# Main_Design.net
KiCad netlist of a schematic drawn in Altium Designer
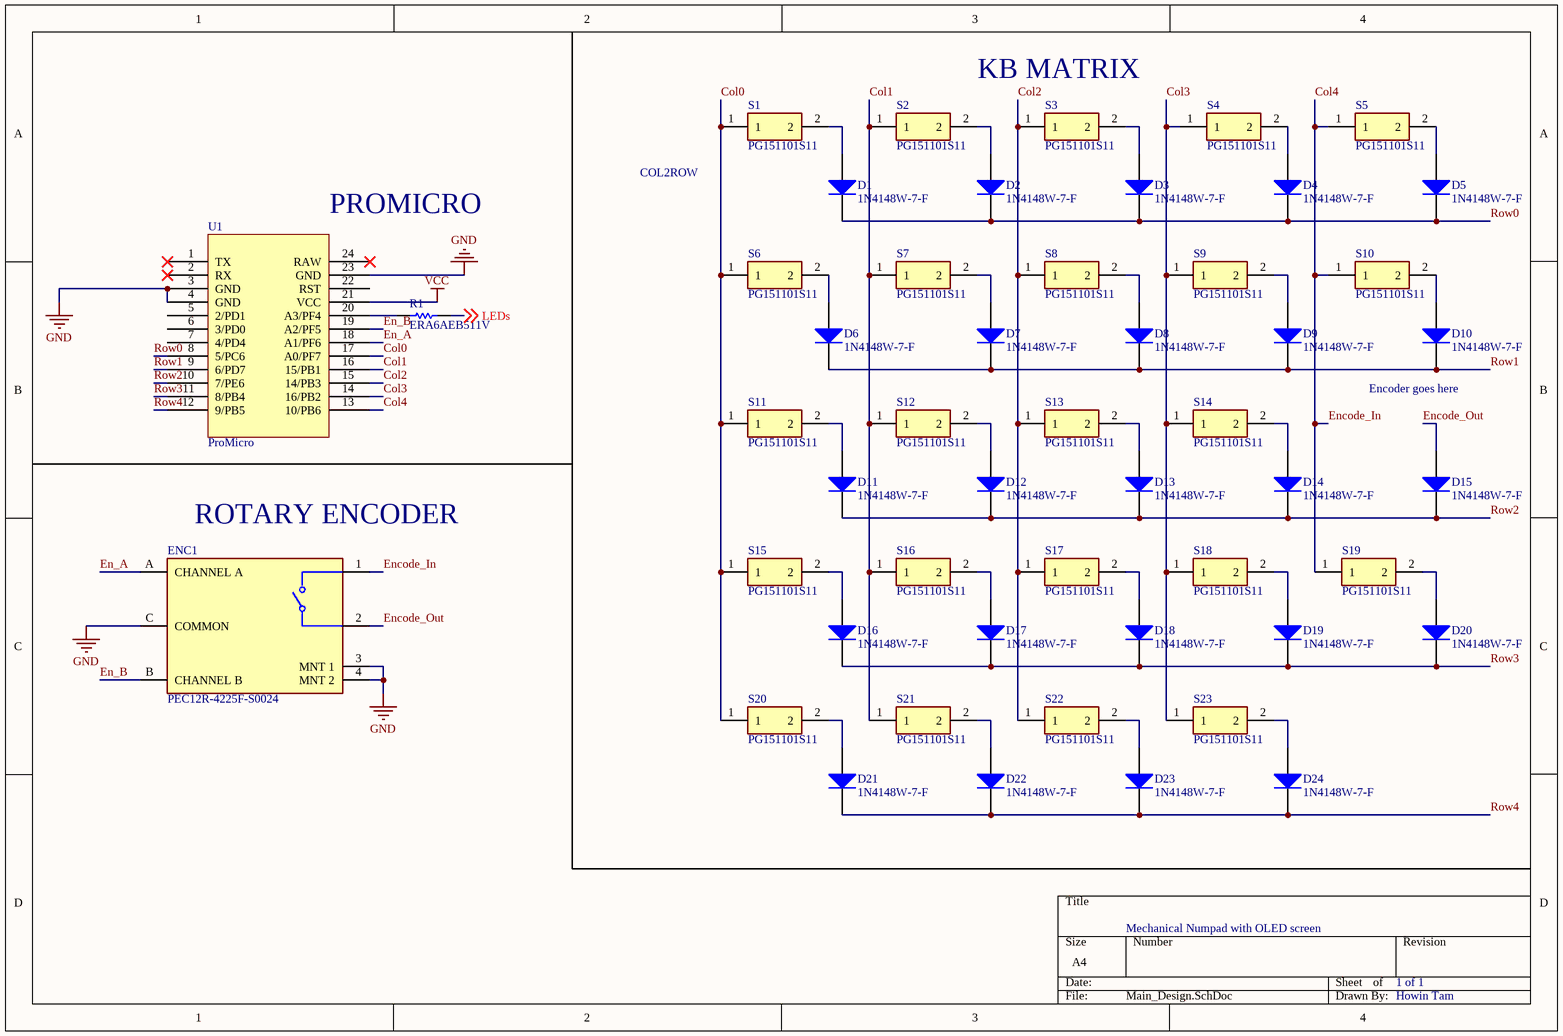
[diagram p0: Main_Design.SchDoc]

(export (version "E")
  (design (tool "Eeschema 10.0.6"))
  (components
    (comp (ref "D1")
      (value "1N4148W-7-F")
      (footprint "DIOD-SOD123-2_V")
      (description "Fast Switching Diode, 100 V, 0.15 A, -65 to 150 degC, 2-Pin?SOD123, RoHS, Tape and Reel")
      (fields (field (name "MANUFACTURER") "DiodesIncorporated"))
      (libsource (lib "Altium Content Vault") (part "D-AK-2"))
    )
    (comp (ref "D2")
      (value "1N4148W-7-F")
      (footprint "DIOD-SOD123-2_V")
      (description "Fast Switching Diode, 100 V, 0.15 A, -65 to 150 degC, 2-Pin?SOD123, RoHS, Tape and Reel")
      (fields (field (name "MANUFACTURER") "DiodesIncorporated"))
      (libsource (lib "Altium Content Vault") (part "D-AK-2"))
    )
    (comp (ref "D3")
      (value "1N4148W-7-F")
      (footprint "DIOD-SOD123-2_V")
      (description "Fast Switching Diode, 100 V, 0.15 A, -65 to 150 degC, 2-Pin?SOD123, RoHS, Tape and Reel")
      (fields (field (name "MANUFACTURER") "DiodesIncorporated"))
      (libsource (lib "Altium Content Vault") (part "D-AK-2"))
    )
    (comp (ref "D4")
      (value "1N4148W-7-F")
      (footprint "DIOD-SOD123-2_V")
      (description "Fast Switching Diode, 100 V, 0.15 A, -65 to 150 degC, 2-Pin?SOD123, RoHS, Tape and Reel")
      (fields (field (name "MANUFACTURER") "DiodesIncorporated"))
      (libsource (lib "Altium Content Vault") (part "D-AK-2"))
    )
    (comp (ref "D5")
      (value "1N4148W-7-F")
      (footprint "DIOD-SOD123-2_V")
      (description "Fast Switching Diode, 100 V, 0.15 A, -65 to 150 degC, 2-Pin?SOD123, RoHS, Tape and Reel")
      (fields (field (name "MANUFACTURER") "DiodesIncorporated"))
      (libsource (lib "Altium Content Vault") (part "D-AK-2"))
    )
    (comp (ref "D6")
      (value "1N4148W-7-F")
      (footprint "DIOD-SOD123-2_V")
      (description "Fast Switching Diode, 100 V, 0.15 A, -65 to 150 degC, 2-Pin?SOD123, RoHS, Tape and Reel")
      (fields (field (name "MANUFACTURER") "DiodesIncorporated"))
      (libsource (lib "Altium Content Vault") (part "D-AK-2"))
    )
    (comp (ref "D7")
      (value "1N4148W-7-F")
      (footprint "DIOD-SOD123-2_V")
      (description "Fast Switching Diode, 100 V, 0.15 A, -65 to 150 degC, 2-Pin?SOD123, RoHS, Tape and Reel")
      (fields (field (name "MANUFACTURER") "DiodesIncorporated"))
      (libsource (lib "Altium Content Vault") (part "D-AK-2"))
    )
    (comp (ref "D8")
      (value "1N4148W-7-F")
      (footprint "DIOD-SOD123-2_V")
      (description "Fast Switching Diode, 100 V, 0.15 A, -65 to 150 degC, 2-Pin?SOD123, RoHS, Tape and Reel")
      (fields (field (name "MANUFACTURER") "DiodesIncorporated"))
      (libsource (lib "Altium Content Vault") (part "D-AK-2"))
    )
    (comp (ref "D9")
      (value "1N4148W-7-F")
      (footprint "DIOD-SOD123-2_V")
      (description "Fast Switching Diode, 100 V, 0.15 A, -65 to 150 degC, 2-Pin?SOD123, RoHS, Tape and Reel")
      (fields (field (name "MANUFACTURER") "DiodesIncorporated"))
      (libsource (lib "Altium Content Vault") (part "D-AK-2"))
    )
    (comp (ref "D10")
      (value "1N4148W-7-F")
      (footprint "DIOD-SOD123-2_V")
      (description "Fast Switching Diode, 100 V, 0.15 A, -65 to 150 degC, 2-Pin?SOD123, RoHS, Tape and Reel")
      (fields (field (name "MANUFACTURER") "DiodesIncorporated"))
      (libsource (lib "Altium Content Vault") (part "D-AK-2"))
    )
    (comp (ref "D11")
      (value "1N4148W-7-F")
      (footprint "DIOD-SOD123-2_V")
      (description "Fast Switching Diode, 100 V, 0.15 A, -65 to 150 degC, 2-Pin?SOD123, RoHS, Tape and Reel")
      (fields (field (name "MANUFACTURER") "DiodesIncorporated"))
      (libsource (lib "Altium Content Vault") (part "D-AK-2"))
    )
    (comp (ref "D12")
      (value "1N4148W-7-F")
      (footprint "DIOD-SOD123-2_V")
      (description "Fast Switching Diode, 100 V, 0.15 A, -65 to 150 degC, 2-Pin?SOD123, RoHS, Tape and Reel")
      (fields (field (name "MANUFACTURER") "DiodesIncorporated"))
      (libsource (lib "Altium Content Vault") (part "D-AK-2"))
    )
    (comp (ref "D13")
      (value "1N4148W-7-F")
      (footprint "DIOD-SOD123-2_V")
      (description "Fast Switching Diode, 100 V, 0.15 A, -65 to 150 degC, 2-Pin?SOD123, RoHS, Tape and Reel")
      (fields (field (name "MANUFACTURER") "DiodesIncorporated"))
      (libsource (lib "Altium Content Vault") (part "D-AK-2"))
    )
    (comp (ref "D14")
      (value "1N4148W-7-F")
      (footprint "DIOD-SOD123-2_V")
      (description "Fast Switching Diode, 100 V, 0.15 A, -65 to 150 degC, 2-Pin?SOD123, RoHS, Tape and Reel")
      (fields (field (name "MANUFACTURER") "DiodesIncorporated"))
      (libsource (lib "Altium Content Vault") (part "D-AK-2"))
    )
    (comp (ref "D15")
      (value "1N4148W-7-F")
      (footprint "DIOD-SOD123-2_V")
      (description "Fast Switching Diode, 100 V, 0.15 A, -65 to 150 degC, 2-Pin?SOD123, RoHS, Tape and Reel")
      (fields (field (name "MANUFACTURER") "DiodesIncorporated"))
      (libsource (lib "Altium Content Vault") (part "D-AK-2"))
    )
    (comp (ref "D16")
      (value "1N4148W-7-F")
      (footprint "DIOD-SOD123-2_V")
      (description "Fast Switching Diode, 100 V, 0.15 A, -65 to 150 degC, 2-Pin?SOD123, RoHS, Tape and Reel")
      (fields (field (name "MANUFACTURER") "DiodesIncorporated"))
      (libsource (lib "Altium Content Vault") (part "D-AK-2"))
    )
    (comp (ref "D17")
      (value "1N4148W-7-F")
      (footprint "DIOD-SOD123-2_V")
      (description "Fast Switching Diode, 100 V, 0.15 A, -65 to 150 degC, 2-Pin?SOD123, RoHS, Tape and Reel")
      (fields (field (name "MANUFACTURER") "DiodesIncorporated"))
      (libsource (lib "Altium Content Vault") (part "D-AK-2"))
    )
    (comp (ref "D18")
      (value "1N4148W-7-F")
      (footprint "DIOD-SOD123-2_V")
      (description "Fast Switching Diode, 100 V, 0.15 A, -65 to 150 degC, 2-Pin?SOD123, RoHS, Tape and Reel")
      (fields (field (name "MANUFACTURER") "DiodesIncorporated"))
      (libsource (lib "Altium Content Vault") (part "D-AK-2"))
    )
    (comp (ref "D19")
      (value "1N4148W-7-F")
      (footprint "DIOD-SOD123-2_V")
      (description "Fast Switching Diode, 100 V, 0.15 A, -65 to 150 degC, 2-Pin?SOD123, RoHS, Tape and Reel")
      (fields (field (name "MANUFACTURER") "DiodesIncorporated"))
      (libsource (lib "Altium Content Vault") (part "D-AK-2"))
    )
    (comp (ref "D20")
      (value "1N4148W-7-F")
      (footprint "DIOD-SOD123-2_V")
      (description "Fast Switching Diode, 100 V, 0.15 A, -65 to 150 degC, 2-Pin?SOD123, RoHS, Tape and Reel")
      (fields (field (name "MANUFACTURER") "DiodesIncorporated"))
      (libsource (lib "Altium Content Vault") (part "D-AK-2"))
    )
    (comp (ref "D21")
      (value "1N4148W-7-F")
      (footprint "DIOD-SOD123-2_V")
      (description "Fast Switching Diode, 100 V, 0.15 A, -65 to 150 degC, 2-Pin?SOD123, RoHS, Tape and Reel")
      (fields (field (name "MANUFACTURER") "DiodesIncorporated"))
      (libsource (lib "Altium Content Vault") (part "D-AK-2"))
    )
    (comp (ref "D22")
      (value "1N4148W-7-F")
      (footprint "DIOD-SOD123-2_V")
      (description "Fast Switching Diode, 100 V, 0.15 A, -65 to 150 degC, 2-Pin?SOD123, RoHS, Tape and Reel")
      (fields (field (name "MANUFACTURER") "DiodesIncorporated"))
      (libsource (lib "Altium Content Vault") (part "D-AK-2"))
    )
    (comp (ref "D23")
      (value "1N4148W-7-F")
      (footprint "DIOD-SOD123-2_V")
      (description "Fast Switching Diode, 100 V, 0.15 A, -65 to 150 degC, 2-Pin?SOD123, RoHS, Tape and Reel")
      (fields (field (name "MANUFACTURER") "DiodesIncorporated"))
      (libsource (lib "Altium Content Vault") (part "D-AK-2"))
    )
    (comp (ref "D24")
      (value "1N4148W-7-F")
      (footprint "DIOD-SOD123-2_V")
      (description "Fast Switching Diode, 100 V, 0.15 A, -65 to 150 degC, 2-Pin?SOD123, RoHS, Tape and Reel")
      (fields (field (name "MANUFACTURER") "DiodesIncorporated"))
      (libsource (lib "Altium Content Vault") (part "D-AK-2"))
    )
    (comp (ref "ENC1")
      (value "PEC12R-4225F-S0024")
      (footprint "FP-PEC12R-4225F-S0024-MFG")
      (description "ROTARY ENCODER MECHANICAL 24PPR")
      (libsource (lib "Altium Content Vault") (part "084942c7348c54a7e5fe2df5ed54478"))
    )
    (comp (ref "R1")
      (value "ERA6AEB511V")
      (footprint "RESC2013X60X40ML20T25")
      (fields (field (name "MANUFACTURER") "Panasonic"))
      (libsource (lib "Altium Content Vault") (part "RES"))
    )
    (comp (ref "S1")
      (value "PG151101S11")
      (footprint "PG151101S11:SW_PG151101S11")
      (description "Keyswitch")
      (fields (field (name "MF") "Kailh"))
      (libsource (lib "PG151101S11") (part "PG151101S11"))
    )
    (comp (ref "S2")
      (value "PG151101S11")
      (footprint "PG151101S11:SW_PG151101S11")
      (description "Keyswitch")
      (fields (field (name "MF") "Kailh"))
      (libsource (lib "PG151101S11") (part "PG151101S11"))
    )
    (comp (ref "S3")
      (value "PG151101S11")
      (footprint "PG151101S11:SW_PG151101S11")
      (description "Keyswitch")
      (fields (field (name "MF") "Kailh"))
      (libsource (lib "PG151101S11") (part "PG151101S11"))
    )
    (comp (ref "S4")
      (value "PG151101S11")
      (footprint "PG151101S11:SW_PG151101S11")
      (description "Keyswitch")
      (fields (field (name "MF") "Kailh"))
      (libsource (lib "PG151101S11") (part "PG151101S11"))
    )
    (comp (ref "S5")
      (value "PG151101S11")
      (footprint "PG151101S11:SW_PG151101S11")
      (description "Keyswitch")
      (fields (field (name "MF") "Kailh"))
      (libsource (lib "PG151101S11") (part "PG151101S11"))
    )
    (comp (ref "S6")
      (value "PG151101S11")
      (footprint "PG151101S11:SW_PG151101S11")
      (description "Keyswitch")
      (fields (field (name "MF") "Kailh"))
      (libsource (lib "PG151101S11") (part "PG151101S11"))
    )
    (comp (ref "S7")
      (value "PG151101S11")
      (footprint "PG151101S11:SW_PG151101S11")
      (description "Keyswitch")
      (fields (field (name "MF") "Kailh"))
      (libsource (lib "PG151101S11") (part "PG151101S11"))
    )
    (comp (ref "S8")
      (value "PG151101S11")
      (footprint "PG151101S11:SW_PG151101S11")
      (description "Keyswitch")
      (fields (field (name "MF") "Kailh"))
      (libsource (lib "PG151101S11") (part "PG151101S11"))
    )
    (comp (ref "S9")
      (value "PG151101S11")
      (footprint "PG151101S11:SW_PG151101S11")
      (description "Keyswitch")
      (fields (field (name "MF") "Kailh"))
      (libsource (lib "PG151101S11") (part "PG151101S11"))
    )
    (comp (ref "S10")
      (value "PG151101S11")
      (footprint "PG151101S11:SW_PG151101S11")
      (description "Keyswitch")
      (fields (field (name "MF") "Kailh"))
      (libsource (lib "PG151101S11") (part "PG151101S11"))
    )
    (comp (ref "S11")
      (value "PG151101S11")
      (footprint "PG151101S11:SW_PG151101S11")
      (description "Keyswitch")
      (fields (field (name "MF") "Kailh"))
      (libsource (lib "PG151101S11") (part "PG151101S11"))
    )
    (comp (ref "S12")
      (value "PG151101S11")
      (footprint "PG151101S11:SW_PG151101S11")
      (description "Keyswitch")
      (fields (field (name "MF") "Kailh"))
      (libsource (lib "PG151101S11") (part "PG151101S11"))
    )
    (comp (ref "S13")
      (value "PG151101S11")
      (footprint "PG151101S11:SW_PG151101S11")
      (description "Keyswitch")
      (fields (field (name "MF") "Kailh"))
      (libsource (lib "PG151101S11") (part "PG151101S11"))
    )
    (comp (ref "S14")
      (value "PG151101S11")
      (footprint "PG151101S11:SW_PG151101S11")
      (description "Keyswitch")
      (fields (field (name "MF") "Kailh"))
      (libsource (lib "PG151101S11") (part "PG151101S11"))
    )
    (comp (ref "S15")
      (value "PG151101S11")
      (footprint "PG151101S11:SW_PG151101S11")
      (description "Keyswitch")
      (fields (field (name "MF") "Kailh"))
      (libsource (lib "PG151101S11") (part "PG151101S11"))
    )
    (comp (ref "S16")
      (value "PG151101S11")
      (footprint "PG151101S11:SW_PG151101S11")
      (description "Keyswitch")
      (fields (field (name "MF") "Kailh"))
      (libsource (lib "PG151101S11") (part "PG151101S11"))
    )
    (comp (ref "S17")
      (value "PG151101S11")
      (footprint "PG151101S11:SW_PG151101S11")
      (description "Keyswitch")
      (fields (field (name "MF") "Kailh"))
      (libsource (lib "PG151101S11") (part "PG151101S11"))
    )
    (comp (ref "S18")
      (value "PG151101S11")
      (footprint "PG151101S11:SW_PG151101S11")
      (description "Keyswitch")
      (fields (field (name "MF") "Kailh"))
      (libsource (lib "PG151101S11") (part "PG151101S11"))
    )
    (comp (ref "S19")
      (value "PG151101S11")
      (footprint "PG151101S11:SW_PG151101S11")
      (description "Keyswitch")
      (fields (field (name "MF") "Kailh"))
      (libsource (lib "PG151101S11") (part "PG151101S11"))
    )
    (comp (ref "S20")
      (value "PG151101S11")
      (footprint "PG151101S11:SW_PG151101S11")
      (description "Keyswitch")
      (fields (field (name "MF") "Kailh"))
      (libsource (lib "PG151101S11") (part "PG151101S11"))
    )
    (comp (ref "S21")
      (value "PG151101S11")
      (footprint "PG151101S11:SW_PG151101S11")
      (description "Keyswitch")
      (fields (field (name "MF") "Kailh"))
      (libsource (lib "PG151101S11") (part "PG151101S11"))
    )
    (comp (ref "S22")
      (value "PG151101S11")
      (footprint "PG151101S11:SW_PG151101S11")
      (description "Keyswitch")
      (fields (field (name "MF") "Kailh"))
      (libsource (lib "PG151101S11") (part "PG151101S11"))
    )
    (comp (ref "S23")
      (value "PG151101S11")
      (footprint "PG151101S11:SW_PG151101S11")
      (description "Keyswitch")
      (fields (field (name "MF") "Kailh"))
      (libsource (lib "PG151101S11") (part "PG151101S11"))
    )
    (comp (ref "U1")
      (value "ProMicro")
      (footprint "PCBComponent_1")
      (libsource (lib "ProMicro") (part "Component_1"))
    )
  )
  (nets
    (net (code "1") (name "/Col0") (class "Default")
      (node (ref "S1") (pin "1") (pinfunction "1_1") (pintype "passive"))
      (node (ref "S11") (pin "1") (pinfunction "1_1") (pintype "passive"))
      (node (ref "S15") (pin "1") (pinfunction "1_1") (pintype "passive"))
      (node (ref "S20") (pin "1") (pinfunction "1_1") (pintype "passive"))
      (node (ref "S6") (pin "1") (pinfunction "1_1") (pintype "passive"))
      (node (ref "U1") (pin "17") (pinfunction "A0/PF7_17") (pintype "passive"))
    )
    (net (code "2") (name "/Col1") (class "Default")
      (node (ref "S12") (pin "1") (pinfunction "1_1") (pintype "passive"))
      (node (ref "S16") (pin "1") (pinfunction "1_1") (pintype "passive"))
      (node (ref "S2") (pin "1") (pinfunction "1_1") (pintype "passive"))
      (node (ref "S21") (pin "1") (pinfunction "1_1") (pintype "passive"))
      (node (ref "S7") (pin "1") (pinfunction "1_1") (pintype "passive"))
      (node (ref "U1") (pin "16") (pinfunction "15/PB1_16") (pintype "passive"))
    )
    (net (code "3") (name "/Col2") (class "Default")
      (node (ref "S13") (pin "1") (pinfunction "1_1") (pintype "passive"))
      (node (ref "S17") (pin "1") (pinfunction "1_1") (pintype "passive"))
      (node (ref "S22") (pin "1") (pinfunction "1_1") (pintype "passive"))
      (node (ref "S3") (pin "1") (pinfunction "1_1") (pintype "passive"))
      (node (ref "S8") (pin "1") (pinfunction "1_1") (pintype "passive"))
      (node (ref "U1") (pin "15") (pinfunction "14/PB3_15") (pintype "passive"))
    )
    (net (code "4") (name "/Col3") (class "Default")
      (node (ref "S14") (pin "1") (pinfunction "1_1") (pintype "passive"))
      (node (ref "S18") (pin "1") (pinfunction "1_1") (pintype "passive"))
      (node (ref "S23") (pin "1") (pinfunction "1_1") (pintype "passive"))
      (node (ref "S4") (pin "1") (pinfunction "1_1") (pintype "passive"))
      (node (ref "S9") (pin "1") (pinfunction "1_1") (pintype "passive"))
      (node (ref "U1") (pin "14") (pinfunction "16/PB2_14") (pintype "passive"))
    )
    (net (code "5") (name "/Col4") (class "Default")
      (node (ref "ENC1") (pin "1") (pinfunction "1_1") (pintype "passive"))
      (node (ref "S10") (pin "1") (pinfunction "1_1") (pintype "passive"))
      (node (ref "S19") (pin "1") (pinfunction "1_1") (pintype "passive"))
      (node (ref "S5") (pin "1") (pinfunction "1_1") (pintype "passive"))
      (node (ref "U1") (pin "13") (pinfunction "10/PB6_13") (pintype "passive"))
    )
    (net (code "6") (name "/En_A") (class "Default")
      (node (ref "ENC1") (pin "A") (pinfunction "CHANNEL_A_A") (pintype "passive"))
      (node (ref "U1") (pin "18") (pinfunction "A1/PF6_18") (pintype "passive"))
    )
    (net (code "7") (name "/En_B") (class "Default")
      (node (ref "ENC1") (pin "B") (pinfunction "CHANNEL_B_B") (pintype "passive"))
      (node (ref "U1") (pin "19") (pinfunction "A2/PF5_19") (pintype "passive"))
    )
    (net (code "8") (name "/Encode_Out") (class "Default")
      (node (ref "D15") (pin "1") (pinfunction "A_1") (pintype "passive"))
      (node (ref "ENC1") (pin "2") (pinfunction "2_2") (pintype "passive"))
    )
    (net (code "9") (name "/Row0") (class "Default")
      (node (ref "D1") (pin "2") (pinfunction "K_2") (pintype "passive"))
      (node (ref "D2") (pin "2") (pinfunction "K_2") (pintype "passive"))
      (node (ref "D3") (pin "2") (pinfunction "K_2") (pintype "passive"))
      (node (ref "D4") (pin "2") (pinfunction "K_2") (pintype "passive"))
      (node (ref "D5") (pin "2") (pinfunction "K_2") (pintype "passive"))
      (node (ref "U1") (pin "8") (pinfunction "5/PC6_8") (pintype "passive"))
    )
    (net (code "10") (name "/Row1") (class "Default")
      (node (ref "D10") (pin "2") (pinfunction "K_2") (pintype "passive"))
      (node (ref "D6") (pin "2") (pinfunction "K_2") (pintype "passive"))
      (node (ref "D7") (pin "2") (pinfunction "K_2") (pintype "passive"))
      (node (ref "D8") (pin "2") (pinfunction "K_2") (pintype "passive"))
      (node (ref "D9") (pin "2") (pinfunction "K_2") (pintype "passive"))
      (node (ref "U1") (pin "9") (pinfunction "6/PD7_9") (pintype "passive"))
    )
    (net (code "11") (name "/Row2") (class "Default")
      (node (ref "D11") (pin "2") (pinfunction "K_2") (pintype "passive"))
      (node (ref "D12") (pin "2") (pinfunction "K_2") (pintype "passive"))
      (node (ref "D13") (pin "2") (pinfunction "K_2") (pintype "passive"))
      (node (ref "D14") (pin "2") (pinfunction "K_2") (pintype "passive"))
      (node (ref "D15") (pin "2") (pinfunction "K_2") (pintype "passive"))
      (node (ref "U1") (pin "10") (pinfunction "7/PE6_10") (pintype "passive"))
    )
    (net (code "12") (name "/Row3") (class "Default")
      (node (ref "D16") (pin "2") (pinfunction "K_2") (pintype "passive"))
      (node (ref "D17") (pin "2") (pinfunction "K_2") (pintype "passive"))
      (node (ref "D18") (pin "2") (pinfunction "K_2") (pintype "passive"))
      (node (ref "D19") (pin "2") (pinfunction "K_2") (pintype "passive"))
      (node (ref "D20") (pin "2") (pinfunction "K_2") (pintype "passive"))
      (node (ref "U1") (pin "11") (pinfunction "8/PB4_11") (pintype "passive"))
    )
    (net (code "13") (name "/Row4") (class "Default")
      (node (ref "D21") (pin "2") (pinfunction "K_2") (pintype "passive"))
      (node (ref "D22") (pin "2") (pinfunction "K_2") (pintype "passive"))
      (node (ref "D23") (pin "2") (pinfunction "K_2") (pintype "passive"))
      (node (ref "D24") (pin "2") (pinfunction "K_2") (pintype "passive"))
      (node (ref "U1") (pin "12") (pinfunction "9/PB5_12") (pintype "passive"))
    )
    (net (code "14") (name "GND") (class "Default")
      (node (ref "ENC1") (pin "3") (pinfunction "MNT_1_3") (pintype "passive"))
      (node (ref "ENC1") (pin "4") (pinfunction "MNT_2_4") (pintype "passive"))
      (node (ref "ENC1") (pin "C") (pinfunction "COMMON_C") (pintype "passive"))
      (node (ref "U1") (pin "23") (pinfunction "GND_23") (pintype "passive"))
      (node (ref "U1") (pin "3") (pinfunction "GND_3") (pintype "passive"))
      (node (ref "U1") (pin "4") (pinfunction "GND_4") (pintype "passive"))
    )
    (net (code "15") (name "LEDs") (class "Default")
      (node (ref "R1") (pin "2") (pinfunction "2_2") (pintype "passive"))
    )
    (net (code "16") (name "Net-(D1-A)") (class "Default")
      (node (ref "D1") (pin "1") (pinfunction "A_1") (pintype "passive"))
      (node (ref "S1") (pin "2") (pinfunction "2_2") (pintype "passive"))
    )
    (net (code "17") (name "Net-(D2-A)") (class "Default")
      (node (ref "D2") (pin "1") (pinfunction "A_1") (pintype "passive"))
      (node (ref "S2") (pin "2") (pinfunction "2_2") (pintype "passive"))
    )
    (net (code "18") (name "Net-(D3-A)") (class "Default")
      (node (ref "D3") (pin "1") (pinfunction "A_1") (pintype "passive"))
      (node (ref "S3") (pin "2") (pinfunction "2_2") (pintype "passive"))
    )
    (net (code "19") (name "Net-(D4-A)") (class "Default")
      (node (ref "D4") (pin "1") (pinfunction "A_1") (pintype "passive"))
      (node (ref "S4") (pin "2") (pinfunction "2_2") (pintype "passive"))
    )
    (net (code "20") (name "Net-(D5-A)") (class "Default")
      (node (ref "D5") (pin "1") (pinfunction "A_1") (pintype "passive"))
      (node (ref "S5") (pin "2") (pinfunction "2_2") (pintype "passive"))
    )
    (net (code "21") (name "Net-(D6-A)") (class "Default")
      (node (ref "D6") (pin "1") (pinfunction "A_1") (pintype "passive"))
      (node (ref "S6") (pin "2") (pinfunction "2_2") (pintype "passive"))
    )
    (net (code "22") (name "Net-(D7-A)") (class "Default")
      (node (ref "D7") (pin "1") (pinfunction "A_1") (pintype "passive"))
      (node (ref "S7") (pin "2") (pinfunction "2_2") (pintype "passive"))
    )
    (net (code "23") (name "Net-(D8-A)") (class "Default")
      (node (ref "D8") (pin "1") (pinfunction "A_1") (pintype "passive"))
      (node (ref "S8") (pin "2") (pinfunction "2_2") (pintype "passive"))
    )
    (net (code "24") (name "Net-(D9-A)") (class "Default")
      (node (ref "D9") (pin "1") (pinfunction "A_1") (pintype "passive"))
      (node (ref "S9") (pin "2") (pinfunction "2_2") (pintype "passive"))
    )
    (net (code "25") (name "Net-(D10-A)") (class "Default")
      (node (ref "D10") (pin "1") (pinfunction "A_1") (pintype "passive"))
      (node (ref "S10") (pin "2") (pinfunction "2_2") (pintype "passive"))
    )
    (net (code "26") (name "Net-(D11-A)") (class "Default")
      (node (ref "D11") (pin "1") (pinfunction "A_1") (pintype "passive"))
      (node (ref "S11") (pin "2") (pinfunction "2_2") (pintype "passive"))
    )
    (net (code "27") (name "Net-(D12-A)") (class "Default")
      (node (ref "D12") (pin "1") (pinfunction "A_1") (pintype "passive"))
      (node (ref "S12") (pin "2") (pinfunction "2_2") (pintype "passive"))
    )
    (net (code "28") (name "Net-(D13-A)") (class "Default")
      (node (ref "D13") (pin "1") (pinfunction "A_1") (pintype "passive"))
      (node (ref "S13") (pin "2") (pinfunction "2_2") (pintype "passive"))
    )
    (net (code "29") (name "Net-(D14-A)") (class "Default")
      (node (ref "D14") (pin "1") (pinfunction "A_1") (pintype "passive"))
      (node (ref "S14") (pin "2") (pinfunction "2_2") (pintype "passive"))
    )
    (net (code "30") (name "Net-(D16-A)") (class "Default")
      (node (ref "D16") (pin "1") (pinfunction "A_1") (pintype "passive"))
      (node (ref "S15") (pin "2") (pinfunction "2_2") (pintype "passive"))
    )
    (net (code "31") (name "Net-(D17-A)") (class "Default")
      (node (ref "D17") (pin "1") (pinfunction "A_1") (pintype "passive"))
      (node (ref "S16") (pin "2") (pinfunction "2_2") (pintype "passive"))
    )
    (net (code "32") (name "Net-(D18-A)") (class "Default")
      (node (ref "D18") (pin "1") (pinfunction "A_1") (pintype "passive"))
      (node (ref "S17") (pin "2") (pinfunction "2_2") (pintype "passive"))
    )
    (net (code "33") (name "Net-(D19-A)") (class "Default")
      (node (ref "D19") (pin "1") (pinfunction "A_1") (pintype "passive"))
      (node (ref "S18") (pin "2") (pinfunction "2_2") (pintype "passive"))
    )
    (net (code "34") (name "Net-(D20-A)") (class "Default")
      (node (ref "D20") (pin "1") (pinfunction "A_1") (pintype "passive"))
      (node (ref "S19") (pin "2") (pinfunction "2_2") (pintype "passive"))
    )
    (net (code "35") (name "Net-(D21-A)") (class "Default")
      (node (ref "D21") (pin "1") (pinfunction "A_1") (pintype "passive"))
      (node (ref "S20") (pin "2") (pinfunction "2_2") (pintype "passive"))
    )
    (net (code "36") (name "Net-(D22-A)") (class "Default")
      (node (ref "D22") (pin "1") (pinfunction "A_1") (pintype "passive"))
      (node (ref "S21") (pin "2") (pinfunction "2_2") (pintype "passive"))
    )
    (net (code "37") (name "Net-(D23-A)") (class "Default")
      (node (ref "D23") (pin "1") (pinfunction "A_1") (pintype "passive"))
      (node (ref "S22") (pin "2") (pinfunction "2_2") (pintype "passive"))
    )
    (net (code "38") (name "Net-(D24-A)") (class "Default")
      (node (ref "D24") (pin "1") (pinfunction "A_1") (pintype "passive"))
      (node (ref "S23") (pin "2") (pinfunction "2_2") (pintype "passive"))
    )
    (net (code "39") (name "Net-(U1-A3{slash}PF4)") (class "Default")
      (node (ref "R1") (pin "1") (pinfunction "1_1") (pintype "passive"))
      (node (ref "U1") (pin "20") (pinfunction "A3/PF4_20") (pintype "passive"))
    )
    (net (code "40") (name "VCC") (class "Default")
      (node (ref "U1") (pin "21") (pinfunction "VCC_21") (pintype "passive"))
    )
    (net (code "41") (name "unconnected-(U1-2{slash}PD1-Pad5)") (class "Default")
      (node (ref "U1") (pin "5") (pinfunction "2/PD1_5") (pintype "passive"))
    )
    (net (code "42") (name "unconnected-(U1-3{slash}PD0-Pad6)") (class "Default")
      (node (ref "U1") (pin "6") (pinfunction "3/PD0_6") (pintype "passive"))
    )
    (net (code "43") (name "unconnected-(U1-4{slash}PD4-Pad7)") (class "Default")
      (node (ref "U1") (pin "7") (pinfunction "4/PD4_7") (pintype "passive"))
    )
    (net (code "44") (name "unconnected-(U1-RAW-Pad24)") (class "Default")
      (node (ref "U1") (pin "24") (pinfunction "RAW_24") (pintype "passive+no_connect"))
    )
    (net (code "45") (name "unconnected-(U1-RST-Pad22)") (class "Default")
      (node (ref "U1") (pin "22") (pinfunction "RST_22") (pintype "passive"))
    )
    (net (code "46") (name "unconnected-(U1-RX-Pad2)") (class "Default")
      (node (ref "U1") (pin "2") (pinfunction "RX_2") (pintype "passive+no_connect"))
    )
    (net (code "47") (name "unconnected-(U1-TX-Pad1)") (class "Default")
      (node (ref "U1") (pin "1") (pinfunction "TX_1") (pintype "passive+no_connect"))
    )
  )
)
